# fadecandybreakout.net
KiCad netlist of a schematic drawn in EAGLE
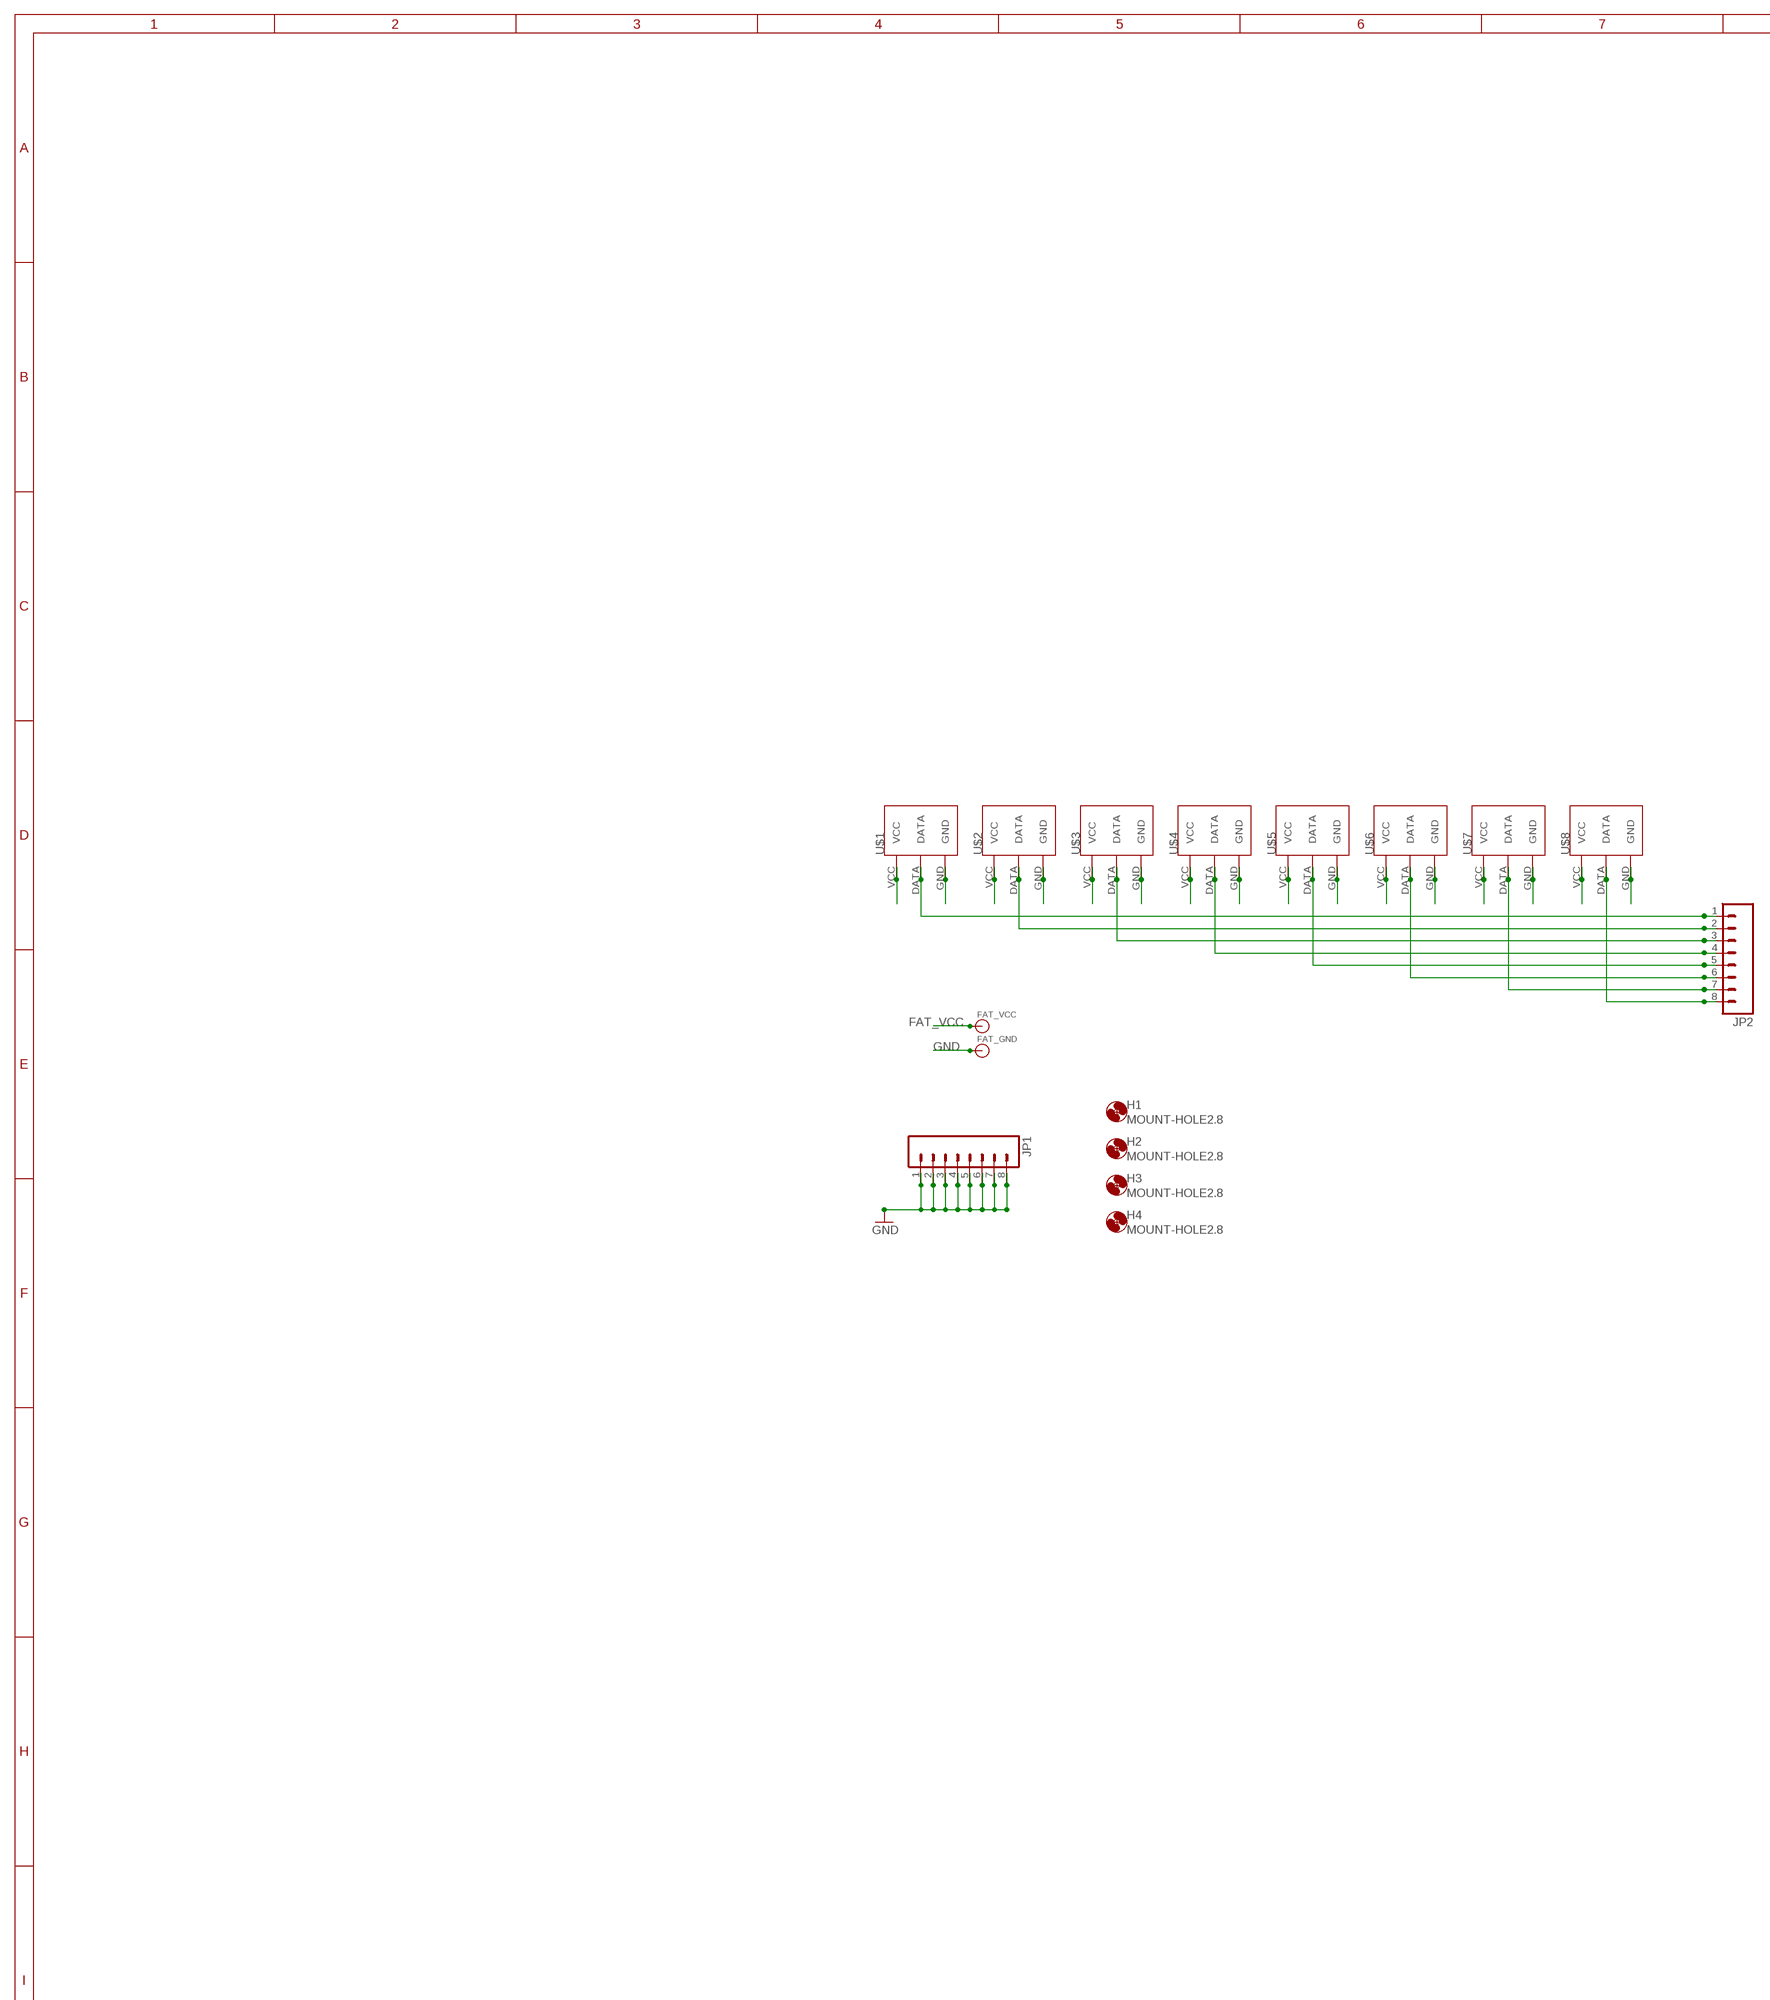
[diagram p0: schematic, sheet 1, part 1 of 2]
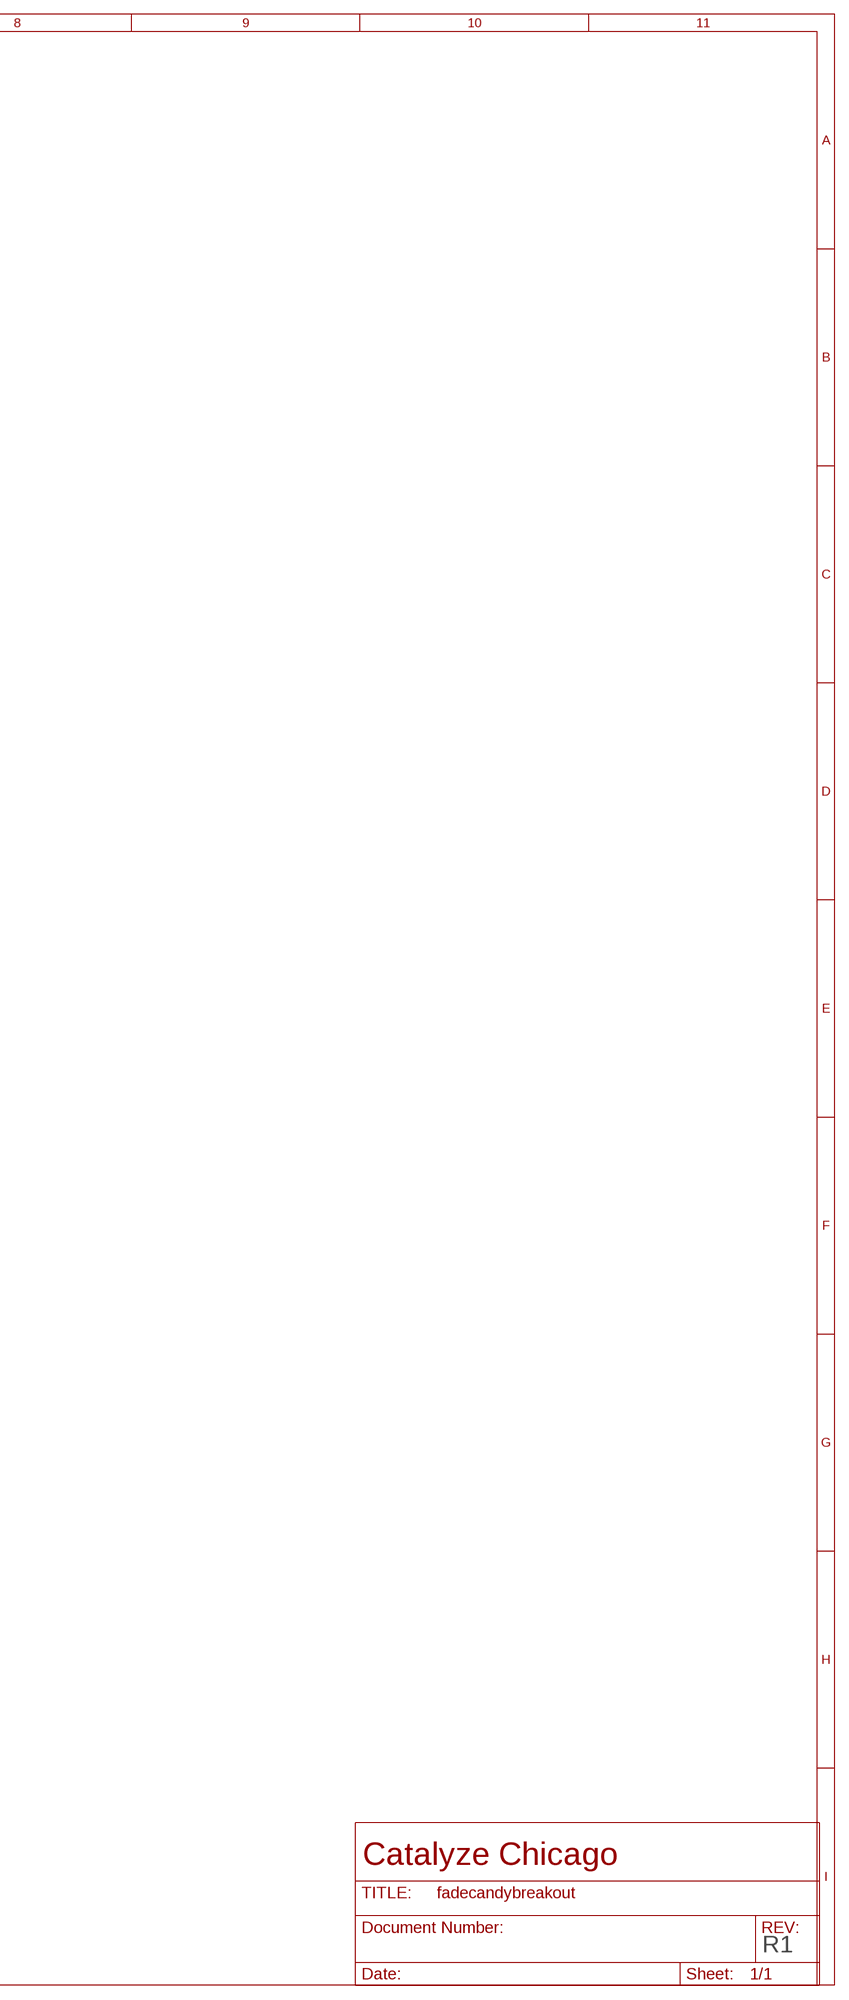
[diagram p1: schematic, sheet 1, part 2 of 2]

(export (version "E")
  (design (tool "Eeschema 10.0.6"))
  (components
    (comp (ref "FAT_GND")
      (value "BANANA_CONN")
      (footprint "eagle-import:BANANA_CONN")
      (libsource (lib "eagle-import") (part "BANANA_CONN"))
    )
    (comp (ref "FAT_VCC")
      (value "BANANA_CONN")
      (footprint "eagle-import:BANANA_CONN")
      (libsource (lib "eagle-import") (part "BANANA_CONN"))
    )
    (comp (ref "H1")
      (value "MOUNT-HOLE2.8")
      (footprint "eagle-import:2,8")
      (libsource (lib "eagle-import") (part "MOUNT-HOLE2.8"))
    )
    (comp (ref "H2")
      (value "MOUNT-HOLE2.8")
      (footprint "eagle-import:2,8")
      (libsource (lib "eagle-import") (part "MOUNT-HOLE2.8"))
    )
    (comp (ref "H3")
      (value "MOUNT-HOLE2.8")
      (footprint "eagle-import:2,8")
      (libsource (lib "eagle-import") (part "MOUNT-HOLE2.8"))
    )
    (comp (ref "H4")
      (value "MOUNT-HOLE2.8")
      (footprint "eagle-import:2,8")
      (libsource (lib "eagle-import") (part "MOUNT-HOLE2.8"))
    )
    (comp (ref "JP1")
      (value "M081X08")
      (footprint "eagle-import:1X08")
      (libsource (lib "eagle-import") (part "M081X08"))
    )
    (comp (ref "JP2")
      (value "M081X08")
      (footprint "eagle-import:1X08")
      (libsource (lib "eagle-import") (part "M081X08"))
    )
    (comp (ref "U$1")
      (value "OSTOQ035450")
      (footprint "eagle-import:OSTOQ035450")
      (libsource (lib "eagle-import") (part "OSTOQ035450"))
    )
    (comp (ref "U$2")
      (value "OSTOQ035450")
      (footprint "eagle-import:OSTOQ035450")
      (libsource (lib "eagle-import") (part "OSTOQ035450"))
    )
    (comp (ref "U$3")
      (value "OSTOQ035450")
      (footprint "eagle-import:OSTOQ035450")
      (libsource (lib "eagle-import") (part "OSTOQ035450"))
    )
    (comp (ref "U$4")
      (value "OSTOQ035450")
      (footprint "eagle-import:OSTOQ035450")
      (libsource (lib "eagle-import") (part "OSTOQ035450"))
    )
    (comp (ref "U$5")
      (value "OSTOQ035450")
      (footprint "eagle-import:OSTOQ035450")
      (libsource (lib "eagle-import") (part "OSTOQ035450"))
    )
    (comp (ref "U$6")
      (value "OSTOQ035450")
      (footprint "eagle-import:OSTOQ035450")
      (libsource (lib "eagle-import") (part "OSTOQ035450"))
    )
    (comp (ref "U$7")
      (value "OSTOQ035450")
      (footprint "eagle-import:OSTOQ035450")
      (libsource (lib "eagle-import") (part "OSTOQ035450"))
    )
    (comp (ref "U$8")
      (value "OSTOQ035450")
      (footprint "eagle-import:OSTOQ035450")
      (libsource (lib "eagle-import") (part "OSTOQ035450"))
    )
  )
  (nets
    (net (code "1") (name "/FAT_VCC") (class "Default")
      (node (ref "FAT_VCC") (pin "P$1") (pinfunction "1_P$1") (pintype "passive"))
      (node (ref "U$1") (pin "VCC") (pinfunction "VCC_VCC") (pintype "bidirectional"))
      (node (ref "U$2") (pin "VCC") (pinfunction "VCC_VCC") (pintype "bidirectional"))
      (node (ref "U$3") (pin "VCC") (pinfunction "VCC_VCC") (pintype "bidirectional"))
      (node (ref "U$4") (pin "VCC") (pinfunction "VCC_VCC") (pintype "bidirectional"))
      (node (ref "U$5") (pin "VCC") (pinfunction "VCC_VCC") (pintype "bidirectional"))
      (node (ref "U$6") (pin "VCC") (pinfunction "VCC_VCC") (pintype "bidirectional"))
      (node (ref "U$7") (pin "VCC") (pinfunction "VCC_VCC") (pintype "bidirectional"))
      (node (ref "U$8") (pin "VCC") (pinfunction "VCC_VCC") (pintype "bidirectional"))
    )
    (net (code "2") (name "GND") (class "Default")
      (node (ref "FAT_GND") (pin "P$1") (pinfunction "1_P$1") (pintype "passive"))
      (node (ref "JP1") (pin "1") (pinfunction "1_1") (pintype "passive"))
      (node (ref "JP1") (pin "2") (pinfunction "2_2") (pintype "passive"))
      (node (ref "JP1") (pin "3") (pinfunction "3_3") (pintype "passive"))
      (node (ref "JP1") (pin "4") (pinfunction "4_4") (pintype "passive"))
      (node (ref "JP1") (pin "5") (pinfunction "5_5") (pintype "passive"))
      (node (ref "JP1") (pin "6") (pinfunction "6_6") (pintype "passive"))
      (node (ref "JP1") (pin "7") (pinfunction "7_7") (pintype "passive"))
      (node (ref "JP1") (pin "8") (pinfunction "8_8") (pintype "passive"))
      (node (ref "U$1") (pin "GND") (pinfunction "GND_GND") (pintype "bidirectional"))
      (node (ref "U$2") (pin "GND") (pinfunction "GND_GND") (pintype "bidirectional"))
      (node (ref "U$3") (pin "GND") (pinfunction "GND_GND") (pintype "bidirectional"))
      (node (ref "U$4") (pin "GND") (pinfunction "GND_GND") (pintype "bidirectional"))
      (node (ref "U$5") (pin "GND") (pinfunction "GND_GND") (pintype "bidirectional"))
      (node (ref "U$6") (pin "GND") (pinfunction "GND_GND") (pintype "bidirectional"))
      (node (ref "U$7") (pin "GND") (pinfunction "GND_GND") (pintype "bidirectional"))
      (node (ref "U$8") (pin "GND") (pinfunction "GND_GND") (pintype "bidirectional"))
    )
    (net (code "3") (name "Net-(JP2-Pad1)") (class "Default")
      (node (ref "JP2") (pin "1") (pinfunction "1_1") (pintype "passive"))
      (node (ref "U$1") (pin "DATA") (pinfunction "DATA_DATA") (pintype "bidirectional"))
    )
    (net (code "4") (name "Net-(JP2-Pad2)") (class "Default")
      (node (ref "JP2") (pin "2") (pinfunction "2_2") (pintype "passive"))
      (node (ref "U$2") (pin "DATA") (pinfunction "DATA_DATA") (pintype "bidirectional"))
    )
    (net (code "5") (name "Net-(JP2-Pad3)") (class "Default")
      (node (ref "JP2") (pin "3") (pinfunction "3_3") (pintype "passive"))
      (node (ref "U$3") (pin "DATA") (pinfunction "DATA_DATA") (pintype "bidirectional"))
    )
    (net (code "6") (name "Net-(JP2-Pad4)") (class "Default")
      (node (ref "JP2") (pin "4") (pinfunction "4_4") (pintype "passive"))
      (node (ref "U$4") (pin "DATA") (pinfunction "DATA_DATA") (pintype "bidirectional"))
    )
    (net (code "7") (name "Net-(JP2-Pad5)") (class "Default")
      (node (ref "JP2") (pin "5") (pinfunction "5_5") (pintype "passive"))
      (node (ref "U$5") (pin "DATA") (pinfunction "DATA_DATA") (pintype "bidirectional"))
    )
    (net (code "8") (name "Net-(JP2-Pad6)") (class "Default")
      (node (ref "JP2") (pin "6") (pinfunction "6_6") (pintype "passive"))
      (node (ref "U$6") (pin "DATA") (pinfunction "DATA_DATA") (pintype "bidirectional"))
    )
    (net (code "9") (name "Net-(JP2-Pad7)") (class "Default")
      (node (ref "JP2") (pin "7") (pinfunction "7_7") (pintype "passive"))
      (node (ref "U$7") (pin "DATA") (pinfunction "DATA_DATA") (pintype "bidirectional"))
    )
    (net (code "10") (name "Net-(JP2-Pad8)") (class "Default")
      (node (ref "JP2") (pin "8") (pinfunction "8_8") (pintype "passive"))
      (node (ref "U$8") (pin "DATA") (pinfunction "DATA_DATA") (pintype "bidirectional"))
    )
  )
)
